# MobilityEliminationController.net
KiCad netlist of a schematic drawn in EAGLE
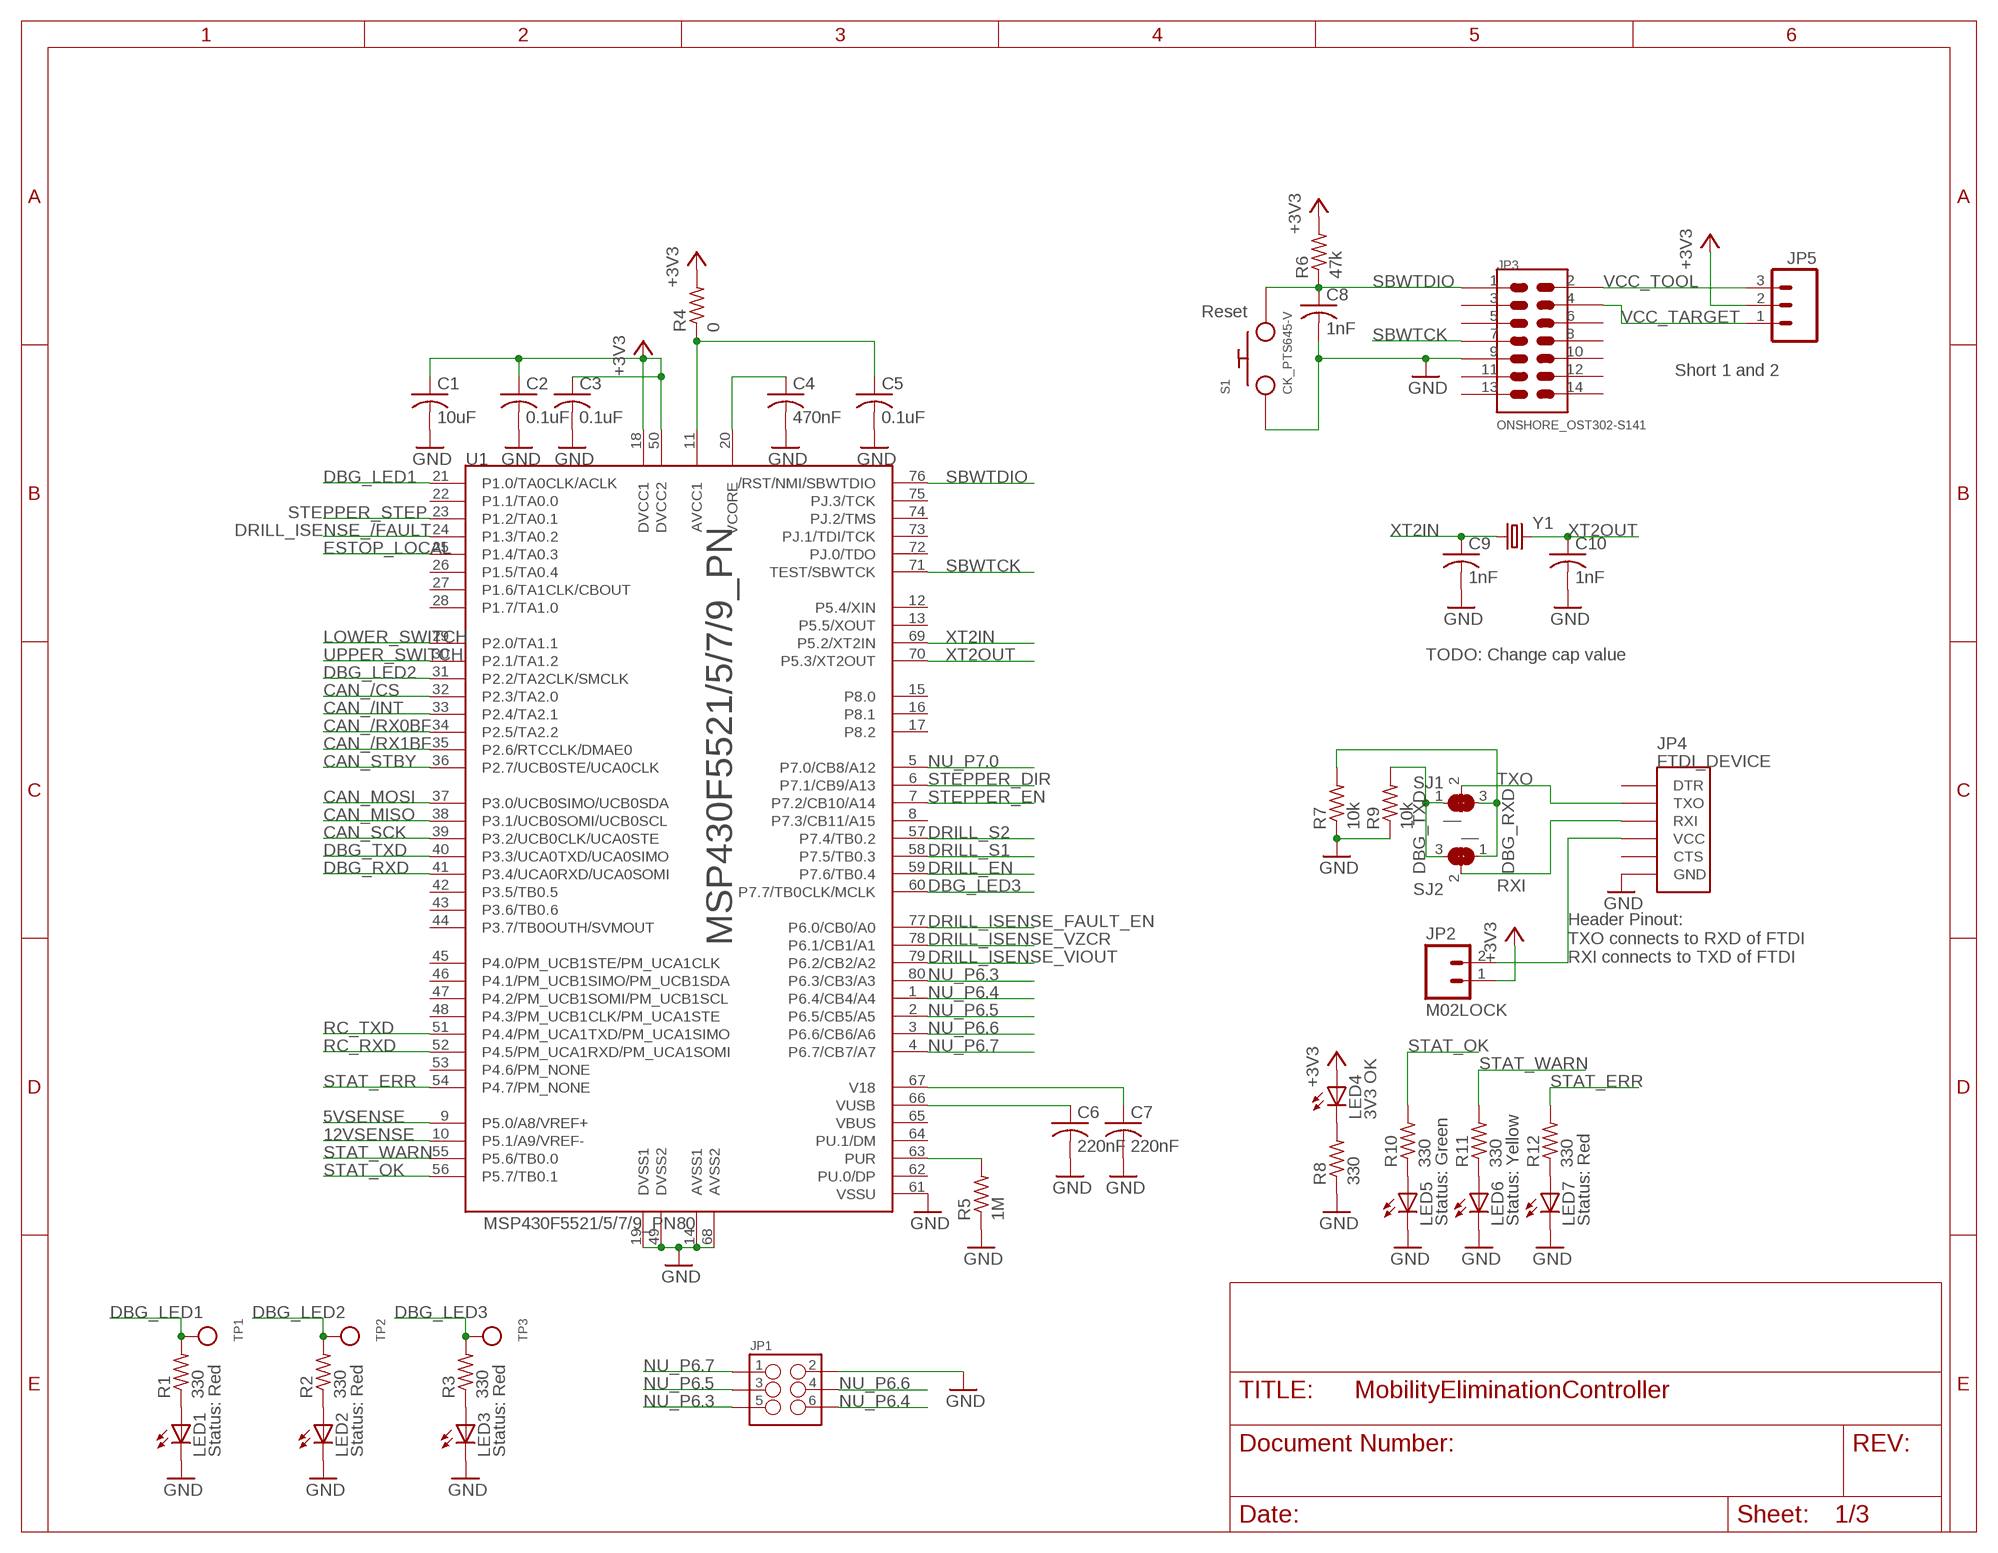
[diagram p0: schematic, sheet 1]
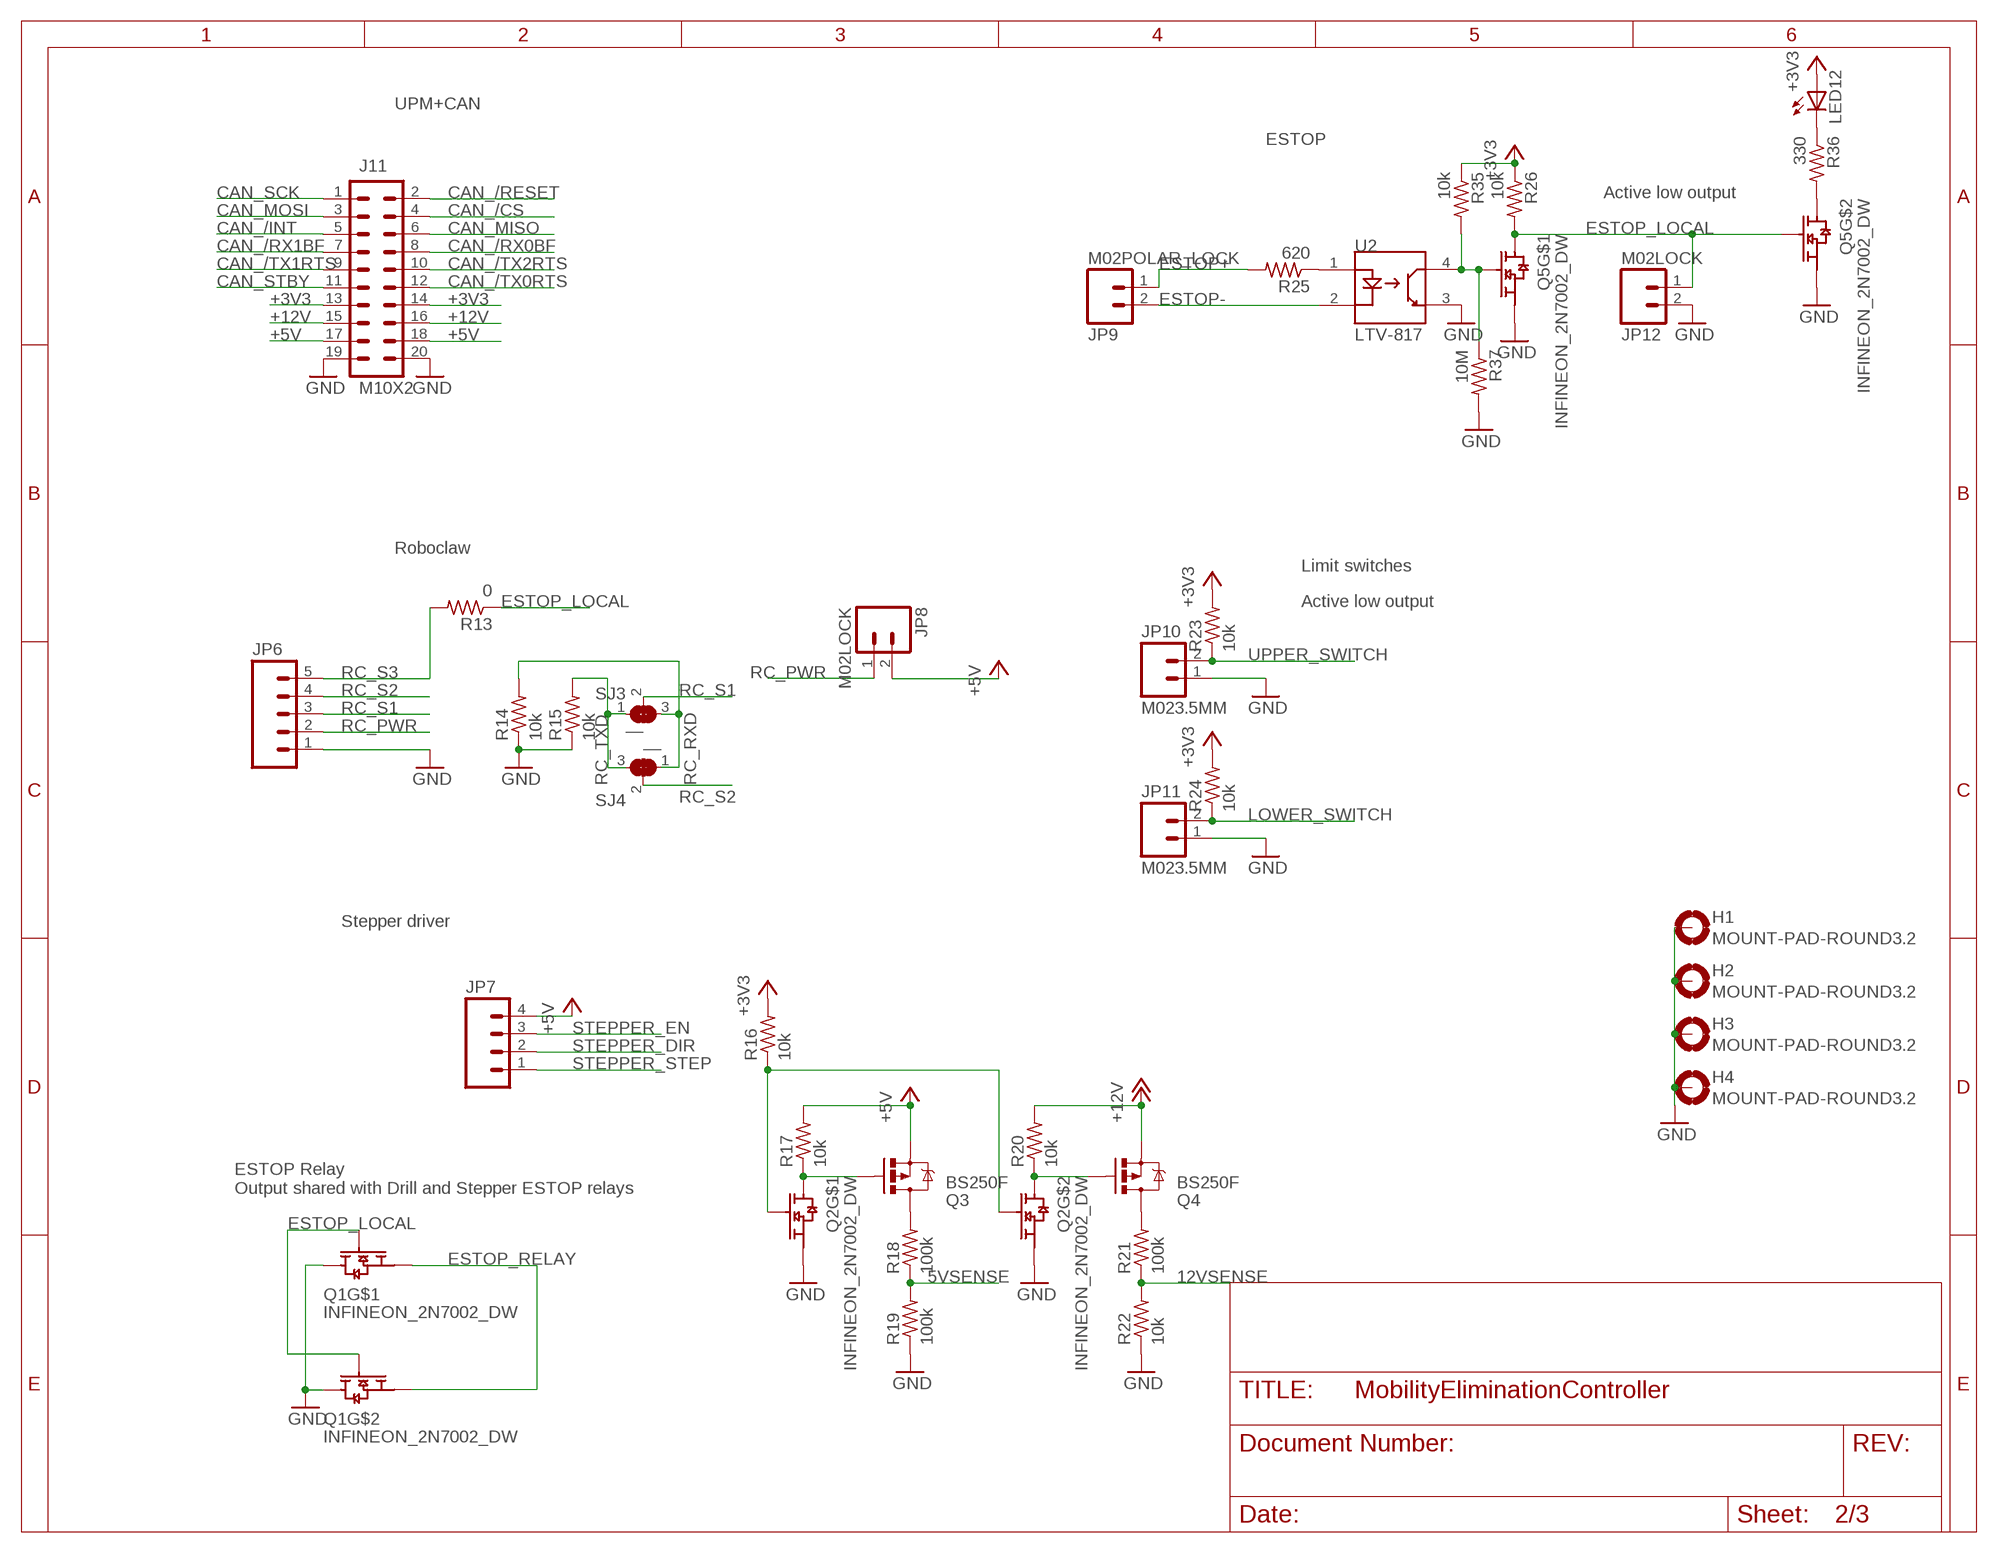
[diagram p1: schematic, sheet 2]
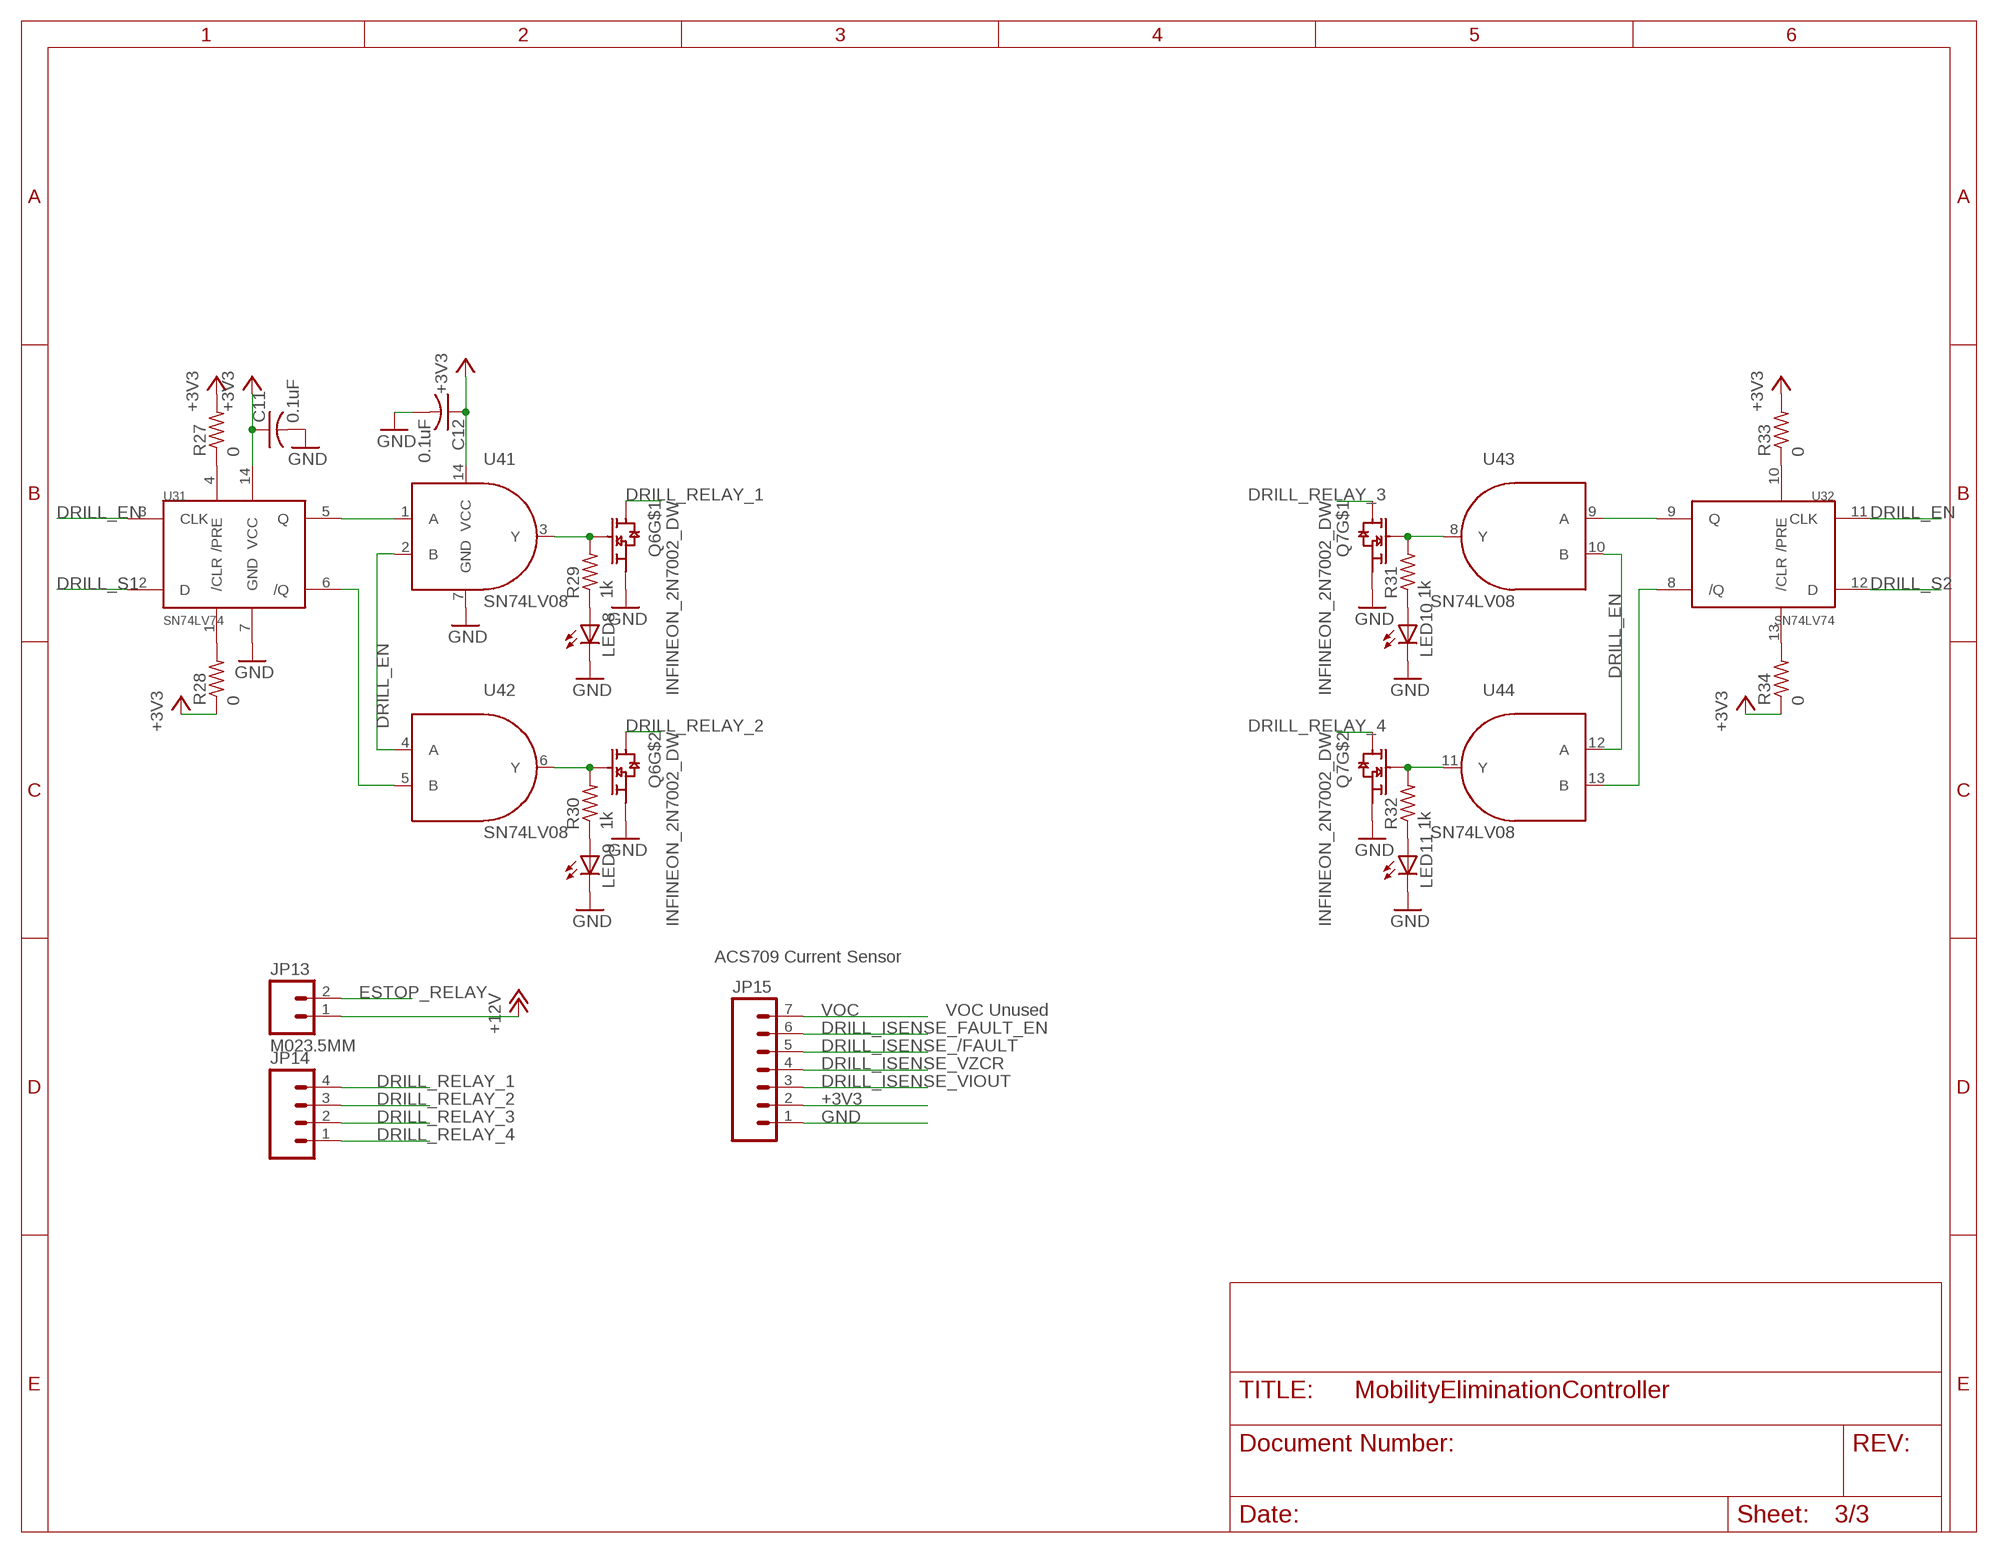
[diagram p2: schematic, sheet 3]

(export (version "E")
  (design (tool "Eeschema 10.0.6"))
  (components
    (comp (ref "C1")
      (value "10uF")
      (footprint "eagle-import:C0805")
      (libsource (lib "eagle-import") (part "C-USC0805"))
    )
    (comp (ref "C2")
      (value "0.1uF")
      (footprint "eagle-import:C0603")
      (libsource (lib "eagle-import") (part "C-USC0603"))
    )
    (comp (ref "C3")
      (value "0.1uF")
      (footprint "eagle-import:C0603")
      (libsource (lib "eagle-import") (part "C-USC0603"))
    )
    (comp (ref "C4")
      (value "470nF")
      (footprint "eagle-import:C0603")
      (libsource (lib "eagle-import") (part "C-USC0603"))
    )
    (comp (ref "C5")
      (value "0.1uF")
      (footprint "eagle-import:C0603")
      (libsource (lib "eagle-import") (part "C-USC0603"))
    )
    (comp (ref "C6")
      (value "220nF")
      (footprint "eagle-import:C0603")
      (libsource (lib "eagle-import") (part "C-USC0603"))
    )
    (comp (ref "C7")
      (value "220nF")
      (footprint "eagle-import:C0603")
      (libsource (lib "eagle-import") (part "C-USC0603"))
    )
    (comp (ref "C8")
      (value "1nF")
      (footprint "eagle-import:C0603")
      (libsource (lib "eagle-import") (part "C-USC0603"))
    )
    (comp (ref "C9")
      (value "1nF")
      (footprint "eagle-import:C0603")
      (libsource (lib "eagle-import") (part "C-USC0603"))
    )
    (comp (ref "C10")
      (value "1nF")
      (footprint "eagle-import:C0603")
      (libsource (lib "eagle-import") (part "C-USC0603"))
    )
    (comp (ref "JP1")
      (value "M03X22X3_SILK_SM")
      (footprint "eagle-import:2X3")
      (libsource (lib "eagle-import") (part "M03X22X3_SILK_SM"))
    )
    (comp (ref "JP2")
      (value "M02LOCK")
      (footprint "eagle-import:1X02_LOCK")
      (libsource (lib "eagle-import") (part "M02LOCK"))
    )
    (comp (ref "JP3")
      (value "ONSHORE_OST302-S141")
      (footprint "eagle-import:ONSHORE_OST302-S141")
      (libsource (lib "eagle-import") (part "ONSHORE_OST302-S141"))
    )
    (comp (ref "JP4")
      (value "FTDI_DEVICE")
      (footprint "eagle-import:FTDI_DEVICE_SIDE")
      (libsource (lib "eagle-import") (part "FTDI_DEVICE"))
    )
    (comp (ref "JP5")
      (value "M03LOCK")
      (footprint "eagle-import:1X03_LOCK")
      (libsource (lib "eagle-import") (part "M03LOCK"))
    )
    (comp (ref "LED1")
      (value "Status: Red")
      (footprint "eagle-import:LED-0603")
      (libsource (lib "eagle-import") (part "LED0603"))
    )
    (comp (ref "LED2")
      (value "Status: Red")
      (footprint "eagle-import:LED-0603")
      (libsource (lib "eagle-import") (part "LED0603"))
    )
    (comp (ref "LED3")
      (value "Status: Red")
      (footprint "eagle-import:LED-0603")
      (libsource (lib "eagle-import") (part "LED0603"))
    )
    (comp (ref "LED4")
      (value "3V3 OK")
      (footprint "eagle-import:LED-0603")
      (libsource (lib "eagle-import") (part "LED0603"))
    )
    (comp (ref "LED5")
      (value "Status: Green")
      (footprint "eagle-import:LED-0603")
      (libsource (lib "eagle-import") (part "LED0603"))
    )
    (comp (ref "LED6")
      (value "Status: Yellow")
      (footprint "eagle-import:LED-0603")
      (libsource (lib "eagle-import") (part "LED0603"))
    )
    (comp (ref "LED7")
      (value "Status: Red")
      (footprint "eagle-import:LED-0603")
      (libsource (lib "eagle-import") (part "LED0603"))
    )
    (comp (ref "R1")
      (value "330")
      (footprint "eagle-import:R0603")
      (libsource (lib "eagle-import") (part "R-US_R0603"))
    )
    (comp (ref "R2")
      (value "330")
      (footprint "eagle-import:R0603")
      (libsource (lib "eagle-import") (part "R-US_R0603"))
    )
    (comp (ref "R3")
      (value "330")
      (footprint "eagle-import:R0603")
      (libsource (lib "eagle-import") (part "R-US_R0603"))
    )
    (comp (ref "R4")
      (value "0")
      (footprint "eagle-import:R0603")
      (libsource (lib "eagle-import") (part "R-US_R0603"))
    )
    (comp (ref "R5")
      (value "1M")
      (footprint "eagle-import:R0603")
      (libsource (lib "eagle-import") (part "R-US_R0603"))
    )
    (comp (ref "R6")
      (value "47k")
      (footprint "eagle-import:R0603")
      (libsource (lib "eagle-import") (part "R-US_R0603"))
    )
    (comp (ref "R7")
      (value "10k")
      (footprint "eagle-import:R0603")
      (libsource (lib "eagle-import") (part "R-US_R0603"))
    )
    (comp (ref "R8")
      (value "330")
      (footprint "eagle-import:R0603")
      (libsource (lib "eagle-import") (part "R-US_R0603"))
    )
    (comp (ref "R9")
      (value "10k")
      (footprint "eagle-import:R0603")
      (libsource (lib "eagle-import") (part "R-US_R0603"))
    )
    (comp (ref "R10")
      (value "330")
      (footprint "eagle-import:R0603")
      (libsource (lib "eagle-import") (part "R-US_R0603"))
    )
    (comp (ref "R11")
      (value "330")
      (footprint "eagle-import:R0603")
      (libsource (lib "eagle-import") (part "R-US_R0603"))
    )
    (comp (ref "R12")
      (value "330")
      (footprint "eagle-import:R0603")
      (libsource (lib "eagle-import") (part "R-US_R0603"))
    )
    (comp (ref "S1")
      (value "CK_PTS645-V")
      (footprint "eagle-import:CK_PTS645-V")
      (libsource (lib "eagle-import") (part "CK_PTS645-V"))
    )
    (comp (ref "SJ1")
      (value "SOLDERJUMPER_2WAY0603")
      (footprint "eagle-import:SOLDERJUMPER_2WAY_OPEN_0603")
      (libsource (lib "eagle-import") (part "SOLDERJUMPER_2WAY0603"))
    )
    (comp (ref "SJ2")
      (value "SOLDERJUMPER_2WAY0603")
      (footprint "eagle-import:SOLDERJUMPER_2WAY_OPEN_0603")
      (libsource (lib "eagle-import") (part "SOLDERJUMPER_2WAY0603"))
    )
    (comp (ref "TP1")
      (value "TESTPOINT0.1\"")
      (footprint "eagle-import:1X01_ROUND")
      (libsource (lib "eagle-import") (part "TESTPOINT0.1{dblquote}"))
    )
    (comp (ref "TP2")
      (value "TESTPOINT0.1\"")
      (footprint "eagle-import:1X01_ROUND")
      (libsource (lib "eagle-import") (part "TESTPOINT0.1{dblquote}"))
    )
    (comp (ref "TP3")
      (value "TESTPOINT0.1\"")
      (footprint "eagle-import:1X01_ROUND")
      (libsource (lib "eagle-import") (part "TESTPOINT0.1{dblquote}"))
    )
    (comp (ref "U1")
      (value "MSP430F5521/5/7/9_PN80")
      (footprint "eagle-import:PN80")
      (libsource (lib "eagle-import") (part "MSP430F5521/5/7/9_PN80"))
    )
    (comp (ref "Y1")
      (value "CRYSTALHC49UV")
      (footprint "eagle-import:HC49U-V")
      (libsource (lib "eagle-import") (part "CRYSTALHC49UV"))
    )
    (comp (ref "C11")
      (value "0.1uF")
      (footprint "eagle-import:C0603")
      (libsource (lib "eagle-import") (part "C-USC0603"))
    )
    (comp (ref "C12")
      (value "0.1uF")
      (footprint "eagle-import:C0603")
      (libsource (lib "eagle-import") (part "C-USC0603"))
    )
    (comp (ref "JP13")
      (value "M023.5MM")
      (footprint "eagle-import:SCREWTERMINAL-3.5MM-2")
      (libsource (lib "eagle-import") (part "M023.5MM"))
    )
    (comp (ref "JP14")
      (value "M04SCREW")
      (footprint "eagle-import:SCREWTERMINAL-3.5MM-4")
      (libsource (lib "eagle-import") (part "M04SCREW"))
    )
    (comp (ref "JP15")
      (value "M07")
      (footprint "eagle-import:1X07")
      (libsource (lib "eagle-import") (part "M07"))
    )
    (comp (ref "LED8")
      (value "LED0603")
      (footprint "eagle-import:LED-0603")
      (libsource (lib "eagle-import") (part "LED0603"))
    )
    (comp (ref "LED9")
      (value "LED0603")
      (footprint "eagle-import:LED-0603")
      (libsource (lib "eagle-import") (part "LED0603"))
    )
    (comp (ref "LED10")
      (value "LED0603")
      (footprint "eagle-import:LED-0603")
      (libsource (lib "eagle-import") (part "LED0603"))
    )
    (comp (ref "LED11")
      (value "LED0603")
      (footprint "eagle-import:LED-0603")
      (libsource (lib "eagle-import") (part "LED0603"))
    )
    (comp (ref "Q6")
      (value "INFINEON_2N7002_DW")
      (footprint "eagle-import:INFINEON_SOT363")
      (libsource (lib "eagle-import") (part "INFINEON_2N7002_DW"))
    )
    (comp (ref "Q7")
      (value "INFINEON_2N7002_DW")
      (footprint "eagle-import:INFINEON_SOT363")
      (libsource (lib "eagle-import") (part "INFINEON_2N7002_DW"))
    )
    (comp (ref "R27")
      (value "0")
      (footprint "eagle-import:R0603")
      (libsource (lib "eagle-import") (part "R-US_R0603"))
    )
    (comp (ref "R28")
      (value "0")
      (footprint "eagle-import:R0603")
      (libsource (lib "eagle-import") (part "R-US_R0603"))
    )
    (comp (ref "R29")
      (value "1k")
      (footprint "eagle-import:R0603")
      (libsource (lib "eagle-import") (part "R-US_R0603"))
    )
    (comp (ref "R30")
      (value "1k")
      (footprint "eagle-import:R0603")
      (libsource (lib "eagle-import") (part "R-US_R0603"))
    )
    (comp (ref "R31")
      (value "1k")
      (footprint "eagle-import:R0603")
      (libsource (lib "eagle-import") (part "R-US_R0603"))
    )
    (comp (ref "R32")
      (value "1k")
      (footprint "eagle-import:R0603")
      (libsource (lib "eagle-import") (part "R-US_R0603"))
    )
    (comp (ref "R33")
      (value "0")
      (footprint "eagle-import:R0603")
      (libsource (lib "eagle-import") (part "R-US_R0603"))
    )
    (comp (ref "R34")
      (value "0")
      (footprint "eagle-import:R0603")
      (libsource (lib "eagle-import") (part "R-US_R0603"))
    )
    (comp (ref "U3")
      (value "SN74LV74")
      (footprint "eagle-import:TI_D_R-PDSO-G14_SOIC14")
      (libsource (lib "eagle-import") (part "SN74LV74"))
    )
    (comp (ref "U4")
      (value "SN74LV08")
      (footprint "eagle-import:TI_D_R-PDSO-G14_SOIC14")
      (libsource (lib "eagle-import") (part "SN74LV08"))
    )
    (comp (ref "H1")
      (value "MOUNT-PAD-ROUND3.2")
      (footprint "eagle-import:3,2-PAD")
      (libsource (lib "eagle-import") (part "MOUNT-PAD-ROUND3.2"))
    )
    (comp (ref "H2")
      (value "MOUNT-PAD-ROUND3.2")
      (footprint "eagle-import:3,2-PAD")
      (libsource (lib "eagle-import") (part "MOUNT-PAD-ROUND3.2"))
    )
    (comp (ref "H3")
      (value "MOUNT-PAD-ROUND3.2")
      (footprint "eagle-import:3,2-PAD")
      (libsource (lib "eagle-import") (part "MOUNT-PAD-ROUND3.2"))
    )
    (comp (ref "H4")
      (value "MOUNT-PAD-ROUND3.2")
      (footprint "eagle-import:3,2-PAD")
      (libsource (lib "eagle-import") (part "MOUNT-PAD-ROUND3.2"))
    )
    (comp (ref "J11")
      (value "M10X2")
      (footprint "eagle-import:2X10")
      (libsource (lib "eagle-import") (part "M10X2"))
    )
    (comp (ref "JP6")
      (value "M05LOCK")
      (footprint "eagle-import:1X05_LOCK")
      (libsource (lib "eagle-import") (part "M05LOCK"))
    )
    (comp (ref "JP7")
      (value "M04SCREW")
      (footprint "eagle-import:SCREWTERMINAL-3.5MM-4")
      (libsource (lib "eagle-import") (part "M04SCREW"))
    )
    (comp (ref "JP8")
      (value "M02LOCK")
      (footprint "eagle-import:1X02_LOCK")
      (libsource (lib "eagle-import") (part "M02LOCK"))
    )
    (comp (ref "JP9")
      (value "M02POLAR_LOCK")
      (footprint "eagle-import:MOLEX-1X2_LOCK")
      (libsource (lib "eagle-import") (part "M02POLAR_LOCK"))
    )
    (comp (ref "JP10")
      (value "M023.5MM")
      (footprint "eagle-import:SCREWTERMINAL-3.5MM-2")
      (libsource (lib "eagle-import") (part "M023.5MM"))
    )
    (comp (ref "JP11")
      (value "M023.5MM")
      (footprint "eagle-import:SCREWTERMINAL-3.5MM-2")
      (libsource (lib "eagle-import") (part "M023.5MM"))
    )
    (comp (ref "JP12")
      (value "M02LOCK")
      (footprint "eagle-import:1X02_LOCK")
      (libsource (lib "eagle-import") (part "M02LOCK"))
    )
    (comp (ref "LED12")
      (value "LED0603")
      (footprint "eagle-import:LED-0603")
      (libsource (lib "eagle-import") (part "LED0603"))
    )
    (comp (ref "Q1")
      (value "INFINEON_2N7002_DW")
      (footprint "eagle-import:INFINEON_SOT363")
      (libsource (lib "eagle-import") (part "INFINEON_2N7002_DW"))
    )
    (comp (ref "Q2")
      (value "INFINEON_2N7002_DW")
      (footprint "eagle-import:INFINEON_SOT363")
      (libsource (lib "eagle-import") (part "INFINEON_2N7002_DW"))
    )
    (comp (ref "Q3")
      (value "BS250F")
      (footprint "eagle-import:SOT23-3")
      (libsource (lib "eagle-import") (part "MOSFET-PCHANNELSMD"))
    )
    (comp (ref "Q4")
      (value "BS250F")
      (footprint "eagle-import:SOT23-3")
      (libsource (lib "eagle-import") (part "MOSFET-PCHANNELSMD"))
    )
    (comp (ref "Q5")
      (value "INFINEON_2N7002_DW")
      (footprint "eagle-import:INFINEON_SOT363")
      (libsource (lib "eagle-import") (part "INFINEON_2N7002_DW"))
    )
    (comp (ref "R13")
      (value "0")
      (footprint "eagle-import:R0603")
      (libsource (lib "eagle-import") (part "R-US_R0603"))
    )
    (comp (ref "R14")
      (value "10k")
      (footprint "eagle-import:R0603")
      (libsource (lib "eagle-import") (part "R-US_R0603"))
    )
    (comp (ref "R15")
      (value "10k")
      (footprint "eagle-import:R0603")
      (libsource (lib "eagle-import") (part "R-US_R0603"))
    )
    (comp (ref "R16")
      (value "10k")
      (footprint "eagle-import:R0603")
      (libsource (lib "eagle-import") (part "R-US_R0603"))
    )
    (comp (ref "R17")
      (value "10k")
      (footprint "eagle-import:R0603")
      (libsource (lib "eagle-import") (part "R-US_R0603"))
    )
    (comp (ref "R18")
      (value "100k")
      (footprint "eagle-import:R0603")
      (libsource (lib "eagle-import") (part "R-US_R0603"))
    )
    (comp (ref "R19")
      (value "100k")
      (footprint "eagle-import:R0603")
      (libsource (lib "eagle-import") (part "R-US_R0603"))
    )
    (comp (ref "R20")
      (value "10k")
      (footprint "eagle-import:R0603")
      (libsource (lib "eagle-import") (part "R-US_R0603"))
    )
    (comp (ref "R21")
      (value "100k")
      (footprint "eagle-import:R0603")
      (libsource (lib "eagle-import") (part "R-US_R0603"))
    )
    (comp (ref "R22")
      (value "10k")
      (footprint "eagle-import:R0603")
      (libsource (lib "eagle-import") (part "R-US_R0603"))
    )
    (comp (ref "R23")
      (value "10k")
      (footprint "eagle-import:R0603")
      (libsource (lib "eagle-import") (part "R-US_R0603"))
    )
    (comp (ref "R24")
      (value "10k")
      (footprint "eagle-import:R0603")
      (libsource (lib "eagle-import") (part "R-US_R0603"))
    )
    (comp (ref "R25")
      (value "620")
      (footprint "eagle-import:R0603")
      (libsource (lib "eagle-import") (part "R-US_R0603"))
    )
    (comp (ref "R26")
      (value "10k")
      (footprint "eagle-import:R0603")
      (libsource (lib "eagle-import") (part "R-US_R0603"))
    )
    (comp (ref "R35")
      (value "10k")
      (footprint "eagle-import:R0603")
      (libsource (lib "eagle-import") (part "R-US_R0603"))
    )
    (comp (ref "R36")
      (value "330")
      (footprint "eagle-import:R0603")
      (libsource (lib "eagle-import") (part "R-US_R0603"))
    )
    (comp (ref "R37")
      (value "10M")
      (footprint "eagle-import:R0603")
      (libsource (lib "eagle-import") (part "R-US_R0603"))
    )
    (comp (ref "SJ3")
      (value "SOLDERJUMPER_2WAY0603")
      (footprint "eagle-import:SOLDERJUMPER_2WAY_OPEN_0603")
      (libsource (lib "eagle-import") (part "SOLDERJUMPER_2WAY0603"))
    )
    (comp (ref "SJ4")
      (value "SOLDERJUMPER_2WAY0603")
      (footprint "eagle-import:SOLDERJUMPER_2WAY_OPEN_0603")
      (libsource (lib "eagle-import") (part "SOLDERJUMPER_2WAY0603"))
    )
    (comp (ref "U2")
      (value "LTV-817")
      (footprint "eagle-import:LITEON_DIL04_.3")
      (libsource (lib "eagle-import") (part "LTV-817"))
    )
  )
  (nets
    (net (code "1") (name "+3V3") (class "Default")
      (node (ref "C1") (pin "1") (pinfunction "1_1") (pintype "passive"))
      (node (ref "C11") (pin "1") (pinfunction "1_1") (pintype "passive"))
      (node (ref "C12") (pin "1") (pinfunction "1_1") (pintype "passive"))
      (node (ref "C2") (pin "1") (pinfunction "1_1") (pintype "passive"))
      (node (ref "C3") (pin "1") (pinfunction "1_1") (pintype "passive"))
      (node (ref "J11") (pin "13") (pinfunction "13_13") (pintype "passive"))
      (node (ref "J11") (pin "14") (pinfunction "14_14") (pintype "passive"))
      (node (ref "JP15") (pin "2") (pinfunction "2_2") (pintype "passive"))
      (node (ref "JP2") (pin "1") (pinfunction "1_1") (pintype "passive"))
      (node (ref "JP5") (pin "2") (pinfunction "2_2") (pintype "passive"))
      (node (ref "LED12") (pin "A") (pinfunction "A_A") (pintype "passive"))
      (node (ref "LED4") (pin "A") (pinfunction "A_A") (pintype "passive"))
      (node (ref "R16") (pin "2") (pinfunction "2_2") (pintype "passive"))
      (node (ref "R23") (pin "2") (pinfunction "2_2") (pintype "passive"))
      (node (ref "R24") (pin "2") (pinfunction "2_2") (pintype "passive"))
      (node (ref "R26") (pin "1") (pinfunction "1_1") (pintype "passive"))
      (node (ref "R27") (pin "2") (pinfunction "2_2") (pintype "passive"))
      (node (ref "R28") (pin "1") (pinfunction "1_1") (pintype "passive"))
      (node (ref "R33") (pin "2") (pinfunction "2_2") (pintype "passive"))
      (node (ref "R34") (pin "1") (pinfunction "1_1") (pintype "passive"))
      (node (ref "R35") (pin "1") (pinfunction "1_1") (pintype "passive"))
      (node (ref "R4") (pin "2") (pinfunction "2_2") (pintype "passive"))
      (node (ref "R6") (pin "2") (pinfunction "2_2") (pintype "passive"))
      (node (ref "U1") (pin "18") (pinfunction "DVCC1_18") (pintype "bidirectional"))
      (node (ref "U1") (pin "50") (pinfunction "DVCC2_50") (pintype "bidirectional"))
      (node (ref "U3") (pin "14") (pinfunction "VCC_14") (pintype "bidirectional"))
      (node (ref "U4") (pin "14") (pinfunction "VCC_14") (pintype "bidirectional"))
    )
    (net (code "2") (name "+5V") (class "Default")
      (node (ref "J11") (pin "17") (pinfunction "17_17") (pintype "passive"))
      (node (ref "J11") (pin "18") (pinfunction "18_18") (pintype "passive"))
      (node (ref "JP7") (pin "4") (pinfunction "4_4") (pintype "passive"))
      (node (ref "JP8") (pin "2") (pinfunction "2_2") (pintype "passive"))
      (node (ref "Q3") (pin "2") (pinfunction "S_2") (pintype "passive"))
      (node (ref "R17") (pin "2") (pinfunction "2_2") (pintype "passive"))
    )
    (net (code "3") (name "+12V") (class "Default")
      (node (ref "J11") (pin "15") (pinfunction "15_15") (pintype "passive"))
      (node (ref "J11") (pin "16") (pinfunction "16_16") (pintype "passive"))
      (node (ref "JP13") (pin "1") (pinfunction "1_1") (pintype "passive"))
      (node (ref "Q4") (pin "2") (pinfunction "S_2") (pintype "passive"))
      (node (ref "R20") (pin "2") (pinfunction "2_2") (pintype "passive"))
    )
    (net (code "4") (name "5VSENSE") (class "Default")
      (node (ref "R18") (pin "1") (pinfunction "1_1") (pintype "passive"))
      (node (ref "R19") (pin "2") (pinfunction "2_2") (pintype "passive"))
      (node (ref "U1") (pin "9") (pinfunction "P5.0/A8/VREF+_9") (pintype "bidirectional"))
    )
    (net (code "5") (name "12VSENSE") (class "Default")
      (node (ref "R21") (pin "1") (pinfunction "1_1") (pintype "passive"))
      (node (ref "R22") (pin "2") (pinfunction "2_2") (pintype "passive"))
      (node (ref "U1") (pin "10") (pinfunction "P5.1/A9/VREF-_10") (pintype "bidirectional"))
    )
    (net (code "6") (name "CAN_MISO") (class "Default")
      (node (ref "J11") (pin "6") (pinfunction "6_6") (pintype "passive"))
      (node (ref "U1") (pin "38") (pinfunction "P3.1/UCB0SOMI/UCB0SCL_38") (pintype "bidirectional"))
    )
    (net (code "7") (name "CAN_MOSI") (class "Default")
      (node (ref "J11") (pin "3") (pinfunction "3_3") (pintype "passive"))
      (node (ref "U1") (pin "37") (pinfunction "P3.0/UCB0SIMO/UCB0SDA_37") (pintype "bidirectional"))
    )
    (net (code "8") (name "CAN_SCK") (class "Default")
      (node (ref "J11") (pin "1") (pinfunction "1_1") (pintype "passive"))
      (node (ref "U1") (pin "39") (pinfunction "P3.2/UCB0CLK/UCA0STE_39") (pintype "bidirectional"))
    )
    (net (code "9") (name "CAN_STBY") (class "Default")
      (node (ref "J11") (pin "11") (pinfunction "11_11") (pintype "passive"))
      (node (ref "U1") (pin "36") (pinfunction "P2.7/UCB0STE/UCA0CLK_36") (pintype "bidirectional"))
    )
    (net (code "10") (name "CAN_{slash}CS") (class "Default")
      (node (ref "J11") (pin "4") (pinfunction "4_4") (pintype "passive"))
      (node (ref "U1") (pin "32") (pinfunction "P2.3/TA2.0_32") (pintype "bidirectional"))
    )
    (net (code "11") (name "CAN_{slash}INT") (class "Default")
      (node (ref "J11") (pin "5") (pinfunction "5_5") (pintype "passive"))
      (node (ref "U1") (pin "33") (pinfunction "P2.4/TA2.1_33") (pintype "bidirectional"))
    )
    (net (code "12") (name "CAN_{slash}RESET") (class "Default")
      (node (ref "J11") (pin "2") (pinfunction "2_2") (pintype "passive"))
    )
    (net (code "13") (name "CAN_{slash}RX0BF") (class "Default")
      (node (ref "J11") (pin "8") (pinfunction "8_8") (pintype "passive"))
      (node (ref "U1") (pin "34") (pinfunction "P2.5/TA2.2_34") (pintype "bidirectional"))
    )
    (net (code "14") (name "CAN_{slash}RX1BF") (class "Default")
      (node (ref "J11") (pin "7") (pinfunction "7_7") (pintype "passive"))
      (node (ref "U1") (pin "35") (pinfunction "P2.6/RTCCLK/DMAE0_35") (pintype "bidirectional"))
    )
    (net (code "15") (name "CAN_{slash}TX0RTS") (class "Default")
      (node (ref "J11") (pin "12") (pinfunction "12_12") (pintype "passive"))
    )
    (net (code "16") (name "CAN_{slash}TX1RTS") (class "Default")
      (node (ref "J11") (pin "9") (pinfunction "9_9") (pintype "passive"))
    )
    (net (code "17") (name "CAN_{slash}TX2RTS") (class "Default")
      (node (ref "J11") (pin "10") (pinfunction "10_10") (pintype "passive"))
    )
    (net (code "18") (name "DBG_LED1") (class "Default")
      (node (ref "R1") (pin "2") (pinfunction "2_2") (pintype "passive"))
      (node (ref "TP1") (pin "1") (pinfunction "P$1_1") (pintype "bidirectional"))
      (node (ref "U1") (pin "21") (pinfunction "P1.0/TA0CLK/ACLK_21") (pintype "bidirectional"))
    )
    (net (code "19") (name "DBG_LED2") (class "Default")
      (node (ref "R2") (pin "2") (pinfunction "2_2") (pintype "passive"))
      (node (ref "TP2") (pin "1") (pinfunction "P$1_1") (pintype "bidirectional"))
      (node (ref "U1") (pin "31") (pinfunction "P2.2/TA2CLK/SMCLK_31") (pintype "bidirectional"))
    )
    (net (code "20") (name "DBG_LED3") (class "Default")
      (node (ref "R3") (pin "2") (pinfunction "2_2") (pintype "passive"))
      (node (ref "TP3") (pin "1") (pinfunction "P$1_1") (pintype "bidirectional"))
      (node (ref "U1") (pin "60") (pinfunction "P7.7/TB0CLK/MCLK_60") (pintype "bidirectional"))
    )
    (net (code "21") (name "DBG_RXD") (class "Default")
      (node (ref "R7") (pin "2") (pinfunction "2_2") (pintype "passive"))
      (node (ref "SJ1") (pin "3") (pinfunction "3_3") (pintype "passive"))
      (node (ref "SJ2") (pin "1") (pinfunction "1_1") (pintype "passive"))
      (node (ref "U1") (pin "41") (pinfunction "P3.4/UCA0RXD/UCA0SOMI_41") (pintype "bidirectional"))
    )
    (net (code "22") (name "DBG_TXD") (class "Default")
      (node (ref "R9") (pin "2") (pinfunction "2_2") (pintype "passive"))
      (node (ref "SJ1") (pin "1") (pinfunction "1_1") (pintype "passive"))
      (node (ref "SJ2") (pin "3") (pinfunction "3_3") (pintype "passive"))
      (node (ref "U1") (pin "40") (pinfunction "P3.3/UCA0TXD/UCA0SIMO_40") (pintype "bidirectional"))
    )
    (net (code "23") (name "DRILL_EN") (class "Default")
      (node (ref "U1") (pin "59") (pinfunction "P7.6/TB0.4_59") (pintype "bidirectional"))
      (node (ref "U3") (pin "11") (pinfunction "CLK_11") (pintype "bidirectional"))
      (node (ref "U3") (pin "3") (pinfunction "CLK_3") (pintype "bidirectional"))
      (node (ref "U4") (pin "10") (pinfunction "B_10") (pintype "bidirectional"))
      (node (ref "U4") (pin "12") (pinfunction "A_12") (pintype "bidirectional"))
      (node (ref "U4") (pin "2") (pinfunction "B_2") (pintype "bidirectional"))
      (node (ref "U4") (pin "4") (pinfunction "A_4") (pintype "bidirectional"))
    )
    (net (code "24") (name "DRILL_ISENSE_FAULT_EN") (class "Default")
      (node (ref "JP15") (pin "6") (pinfunction "6_6") (pintype "passive"))
      (node (ref "U1") (pin "77") (pinfunction "P6.0/CB0/A0_77") (pintype "bidirectional"))
    )
    (net (code "25") (name "DRILL_ISENSE_VIOUT") (class "Default")
      (node (ref "JP15") (pin "3") (pinfunction "3_3") (pintype "passive"))
      (node (ref "U1") (pin "79") (pinfunction "P6.2/CB2/A2_79") (pintype "bidirectional"))
    )
    (net (code "26") (name "DRILL_ISENSE_VZCR") (class "Default")
      (node (ref "JP15") (pin "4") (pinfunction "4_4") (pintype "passive"))
      (node (ref "U1") (pin "78") (pinfunction "P6.1/CB1/A1_78") (pintype "bidirectional"))
    )
    (net (code "27") (name "DRILL_ISENSE_{slash}FAULT") (class "Default")
      (node (ref "JP15") (pin "5") (pinfunction "5_5") (pintype "passive"))
      (node (ref "U1") (pin "24") (pinfunction "P1.3/TA0.2_24") (pintype "bidirectional"))
    )
    (net (code "28") (name "DRILL_RELAY_1") (class "Default")
      (node (ref "JP14") (pin "4") (pinfunction "4_4") (pintype "passive"))
      (node (ref "Q6") (pin "6") (pinfunction "DRAIN_6") (pintype "bidirectional"))
    )
    (net (code "29") (name "DRILL_RELAY_2") (class "Default")
      (node (ref "JP14") (pin "3") (pinfunction "3_3") (pintype "passive"))
      (node (ref "Q6") (pin "3") (pinfunction "DRAIN_3") (pintype "bidirectional"))
    )
    (net (code "30") (name "DRILL_RELAY_3") (class "Default")
      (node (ref "JP14") (pin "2") (pinfunction "2_2") (pintype "passive"))
      (node (ref "Q7") (pin "6") (pinfunction "DRAIN_6") (pintype "bidirectional"))
    )
    (net (code "31") (name "DRILL_RELAY_4") (class "Default")
      (node (ref "JP14") (pin "1") (pinfunction "1_1") (pintype "passive"))
      (node (ref "Q7") (pin "3") (pinfunction "DRAIN_3") (pintype "bidirectional"))
    )
    (net (code "32") (name "DRILL_S1") (class "Default")
      (node (ref "U1") (pin "58") (pinfunction "P7.5/TB0.3_58") (pintype "bidirectional"))
      (node (ref "U3") (pin "2") (pinfunction "D_2") (pintype "bidirectional"))
    )
    (net (code "33") (name "DRILL_S2") (class "Default")
      (node (ref "U1") (pin "57") (pinfunction "P7.4/TB0.2_57") (pintype "bidirectional"))
      (node (ref "U3") (pin "12") (pinfunction "D_12") (pintype "bidirectional"))
    )
    (net (code "34") (name "ESTOP+") (class "Default")
      (node (ref "JP9") (pin "1") (pinfunction "1_1") (pintype "passive"))
      (node (ref "R25") (pin "2") (pinfunction "2_2") (pintype "passive"))
    )
    (net (code "35") (name "ESTOP-") (class "Default")
      (node (ref "JP9") (pin "2") (pinfunction "2_2") (pintype "passive"))
      (node (ref "U2") (pin "2") (pinfunction "2_2") (pintype "bidirectional"))
    )
    (net (code "36") (name "ESTOP_LOCAL") (class "Default")
      (node (ref "JP12") (pin "1") (pinfunction "1_1") (pintype "passive"))
      (node (ref "Q1") (pin "2") (pinfunction "GATE_2") (pintype "bidirectional"))
      (node (ref "Q1") (pin "5") (pinfunction "GATE_5") (pintype "bidirectional"))
      (node (ref "Q5") (pin "5") (pinfunction "GATE_5") (pintype "bidirectional"))
      (node (ref "Q5") (pin "6") (pinfunction "DRAIN_6") (pintype "bidirectional"))
      (node (ref "R13") (pin "1") (pinfunction "1_1") (pintype "passive"))
      (node (ref "R26") (pin "2") (pinfunction "2_2") (pintype "passive"))
      (node (ref "U1") (pin "25") (pinfunction "P1.4/TA0.3_25") (pintype "bidirectional"))
    )
    (net (code "37") (name "ESTOP_RELAY") (class "Default")
      (node (ref "JP13") (pin "2") (pinfunction "2_2") (pintype "passive"))
      (node (ref "Q1") (pin "1") (pinfunction "SOURCE_1") (pintype "bidirectional"))
      (node (ref "Q1") (pin "4") (pinfunction "SOURCE_4") (pintype "bidirectional"))
    )
    (net (code "38") (name "GND") (class "Default")
      (node (ref "C1") (pin "2") (pinfunction "2_2") (pintype "passive"))
      (node (ref "C10") (pin "2") (pinfunction "2_2") (pintype "passive"))
      (node (ref "C11") (pin "2") (pinfunction "2_2") (pintype "passive"))
      (node (ref "C12") (pin "2") (pinfunction "2_2") (pintype "passive"))
      (node (ref "C2") (pin "2") (pinfunction "2_2") (pintype "passive"))
      (node (ref "C3") (pin "2") (pinfunction "2_2") (pintype "passive"))
      (node (ref "C4") (pin "2") (pinfunction "2_2") (pintype "passive"))
      (node (ref "C5") (pin "2") (pinfunction "2_2") (pintype "passive"))
      (node (ref "C6") (pin "2") (pinfunction "2_2") (pintype "passive"))
      (node (ref "C7") (pin "2") (pinfunction "2_2") (pintype "passive"))
      (node (ref "C8") (pin "2") (pinfunction "2_2") (pintype "passive"))
      (node (ref "C9") (pin "2") (pinfunction "2_2") (pintype "passive"))
      (node (ref "H1") (pin "B3,2") (pinfunction "MOUNT_B3,2") (pintype "passive"))
      (node (ref "H2") (pin "B3,2") (pinfunction "MOUNT_B3,2") (pintype "passive"))
      (node (ref "H3") (pin "B3,2") (pinfunction "MOUNT_B3,2") (pintype "passive"))
      (node (ref "H4") (pin "B3,2") (pinfunction "MOUNT_B3,2") (pintype "passive"))
      (node (ref "J11") (pin "19") (pinfunction "19_19") (pintype "passive"))
      (node (ref "J11") (pin "20") (pinfunction "20_20") (pintype "passive"))
      (node (ref "JP1") (pin "2") (pinfunction "2_2") (pintype "bidirectional"))
      (node (ref "JP10") (pin "1") (pinfunction "1_1") (pintype "passive"))
      (node (ref "JP11") (pin "1") (pinfunction "1_1") (pintype "passive"))
      (node (ref "JP12") (pin "2") (pinfunction "2_2") (pintype "passive"))
      (node (ref "JP15") (pin "1") (pinfunction "1_1") (pintype "passive"))
      (node (ref "JP3") (pin "9") (pinfunction "9_9") (pintype "bidirectional"))
      (node (ref "JP4") (pin "P$6") (pinfunction "GND_P$6") (pintype "bidirectional"))
      (node (ref "JP6") (pin "1") (pinfunction "1_1") (pintype "passive"))
      (node (ref "LED1") (pin "C") (pinfunction "C_C") (pintype "passive"))
      (node (ref "LED10") (pin "C") (pinfunction "C_C") (pintype "passive"))
      (node (ref "LED11") (pin "C") (pinfunction "C_C") (pintype "passive"))
      (node (ref "LED2") (pin "C") (pinfunction "C_C") (pintype "passive"))
      (node (ref "LED3") (pin "C") (pinfunction "C_C") (pintype "passive"))
      (node (ref "LED5") (pin "C") (pinfunction "C_C") (pintype "passive"))
      (node (ref "LED6") (pin "C") (pinfunction "C_C") (pintype "passive"))
      (node (ref "LED7") (pin "C") (pinfunction "C_C") (pintype "passive"))
      (node (ref "LED8") (pin "C") (pinfunction "C_C") (pintype "passive"))
      (node (ref "LED9") (pin "C") (pinfunction "C_C") (pintype "passive"))
      (node (ref "Q1") (pin "3") (pinfunction "DRAIN_3") (pintype "bidirectional"))
      (node (ref "Q1") (pin "6") (pinfunction "DRAIN_6") (pintype "bidirectional"))
      (node (ref "Q2") (pin "1") (pinfunction "SOURCE_1") (pintype "bidirectional"))
      (node (ref "Q2") (pin "4") (pinfunction "SOURCE_4") (pintype "bidirectional"))
      (node (ref "Q5") (pin "1") (pinfunction "SOURCE_1") (pintype "bidirectional"))
      (node (ref "Q5") (pin "4") (pinfunction "SOURCE_4") (pintype "bidirectional"))
      (node (ref "Q6") (pin "1") (pinfunction "SOURCE_1") (pintype "bidirectional"))
      (node (ref "Q6") (pin "4") (pinfunction "SOURCE_4") (pintype "bidirectional"))
      (node (ref "Q7") (pin "1") (pinfunction "SOURCE_1") (pintype "bidirectional"))
      (node (ref "Q7") (pin "4") (pinfunction "SOURCE_4") (pintype "bidirectional"))
      (node (ref "R14") (pin "1") (pinfunction "1_1") (pintype "passive"))
      (node (ref "R15") (pin "1") (pinfunction "1_1") (pintype "passive"))
      (node (ref "R19") (pin "1") (pinfunction "1_1") (pintype "passive"))
      (node (ref "R22") (pin "1") (pinfunction "1_1") (pintype "passive"))
      (node (ref "R37") (pin "2") (pinfunction "2_2") (pintype "passive"))
      (node (ref "R5") (pin "1") (pinfunction "1_1") (pintype "passive"))
      (node (ref "R7") (pin "1") (pinfunction "1_1") (pintype "passive"))
      (node (ref "R8") (pin "1") (pinfunction "1_1") (pintype "passive"))
      (node (ref "R9") (pin "1") (pinfunction "1_1") (pintype "passive"))
      (node (ref "S1") (pin "1") (pinfunction "1_1") (pintype "bidirectional"))
      (node (ref "U1") (pin "14") (pinfunction "AVSS1_14") (pintype "bidirectional"))
      (node (ref "U1") (pin "19") (pinfunction "DVSS1_19") (pintype "bidirectional"))
      (node (ref "U1") (pin "49") (pinfunction "DVSS2_49") (pintype "bidirectional"))
      (node (ref "U1") (pin "61") (pinfunction "VSSU_61") (pintype "bidirectional"))
      (node (ref "U1") (pin "68") (pinfunction "AVSS2_68") (pintype "bidirectional"))
      (node (ref "U2") (pin "3") (pinfunction "3_3") (pintype "bidirectional"))
      (node (ref "U3") (pin "7") (pinfunction "GND_7") (pintype "bidirectional"))
      (node (ref "U4") (pin "7") (pinfunction "GND_7") (pintype "bidirectional"))
    )
    (net (code "39") (name "LOWER_SWITCH") (class "Default")
      (node (ref "JP11") (pin "2") (pinfunction "2_2") (pintype "passive"))
      (node (ref "R24") (pin "1") (pinfunction "1_1") (pintype "passive"))
      (node (ref "U1") (pin "29") (pinfunction "P2.0/TA1.1_29") (pintype "bidirectional"))
    )
    (net (code "40") (name "NU_P6.3") (class "Default")
      (node (ref "JP1") (pin "5") (pinfunction "5_5") (pintype "bidirectional"))
      (node (ref "U1") (pin "80") (pinfunction "P6.3/CB3/A3_80") (pintype "bidirectional"))
    )
    (net (code "41") (name "NU_P6.4") (class "Default")
      (node (ref "JP1") (pin "6") (pinfunction "6_6") (pintype "bidirectional"))
      (node (ref "U1") (pin "1") (pinfunction "P6.4/CB4/A4_1") (pintype "bidirectional"))
    )
    (net (code "42") (name "NU_P6.5") (class "Default")
      (node (ref "JP1") (pin "3") (pinfunction "3_3") (pintype "bidirectional"))
      (node (ref "U1") (pin "2") (pinfunction "P6.5/CB5/A5_2") (pintype "bidirectional"))
    )
    (net (code "43") (name "NU_P6.6") (class "Default")
      (node (ref "JP1") (pin "4") (pinfunction "4_4") (pintype "bidirectional"))
      (node (ref "U1") (pin "3") (pinfunction "P6.6/CB6/A6_3") (pintype "bidirectional"))
    )
    (net (code "44") (name "NU_P6.7") (class "Default")
      (node (ref "JP1") (pin "1") (pinfunction "1_1") (pintype "bidirectional"))
      (node (ref "U1") (pin "4") (pinfunction "P6.7/CB7/A7_4") (pintype "bidirectional"))
    )
    (net (code "45") (name "NU_P7.0") (class "Default")
      (node (ref "U1") (pin "5") (pinfunction "P7.0/CB8/A12_5") (pintype "bidirectional"))
    )
    (net (code "46") (name "Net-(JP4-VCC)") (class "Default")
      (node (ref "JP2") (pin "2") (pinfunction "2_2") (pintype "passive"))
      (node (ref "JP4") (pin "P$4") (pinfunction "VCC_P$4") (pintype "bidirectional"))
    )
    (net (code "47") (name "Net-(LED1-PadA)") (class "Default")
      (node (ref "LED1") (pin "A") (pinfunction "A_A") (pintype "passive"))
      (node (ref "R1") (pin "1") (pinfunction "1_1") (pintype "passive"))
    )
    (net (code "48") (name "Net-(LED2-PadA)") (class "Default")
      (node (ref "LED2") (pin "A") (pinfunction "A_A") (pintype "passive"))
      (node (ref "R2") (pin "1") (pinfunction "1_1") (pintype "passive"))
    )
    (net (code "49") (name "Net-(LED3-PadA)") (class "Default")
      (node (ref "LED3") (pin "A") (pinfunction "A_A") (pintype "passive"))
      (node (ref "R3") (pin "1") (pinfunction "1_1") (pintype "passive"))
    )
    (net (code "50") (name "Net-(LED4-PadC)") (class "Default")
      (node (ref "LED4") (pin "C") (pinfunction "C_C") (pintype "passive"))
      (node (ref "R8") (pin "2") (pinfunction "2_2") (pintype "passive"))
    )
    (net (code "51") (name "Net-(LED5-PadA)") (class "Default")
      (node (ref "LED5") (pin "A") (pinfunction "A_A") (pintype "passive"))
      (node (ref "R10") (pin "1") (pinfunction "1_1") (pintype "passive"))
    )
    (net (code "52") (name "Net-(LED6-PadA)") (class "Default")
      (node (ref "LED6") (pin "A") (pinfunction "A_A") (pintype "passive"))
      (node (ref "R11") (pin "1") (pinfunction "1_1") (pintype "passive"))
    )
    (net (code "53") (name "Net-(LED7-PadA)") (class "Default")
      (node (ref "LED7") (pin "A") (pinfunction "A_A") (pintype "passive"))
      (node (ref "R12") (pin "1") (pinfunction "1_1") (pintype "passive"))
    )
    (net (code "54") (name "Net-(LED8-PadA)") (class "Default")
      (node (ref "LED8") (pin "A") (pinfunction "A_A") (pintype "passive"))
      (node (ref "R29") (pin "1") (pinfunction "1_1") (pintype "passive"))
    )
    (net (code "55") (name "Net-(LED9-PadA)") (class "Default")
      (node (ref "LED9") (pin "A") (pinfunction "A_A") (pintype "passive"))
      (node (ref "R30") (pin "1") (pinfunction "1_1") (pintype "passive"))
    )
    (net (code "56") (name "Net-(LED10-PadA)") (class "Default")
      (node (ref "LED10") (pin "A") (pinfunction "A_A") (pintype "passive"))
      (node (ref "R31") (pin "1") (pinfunction "1_1") (pintype "passive"))
    )
    (net (code "57") (name "Net-(LED11-PadA)") (class "Default")
      (node (ref "LED11") (pin "A") (pinfunction "A_A") (pintype "passive"))
      (node (ref "R32") (pin "1") (pinfunction "1_1") (pintype "passive"))
    )
    (net (code "58") (name "Net-(LED12-PadC)") (class "Default")
      (node (ref "LED12") (pin "C") (pinfunction "C_C") (pintype "passive"))
      (node (ref "R36") (pin "1") (pinfunction "1_1") (pintype "passive"))
    )
    (net (code "59") (name "Net-(Q2A-DRAIN)") (class "Default")
      (node (ref "Q2") (pin "6") (pinfunction "DRAIN_6") (pintype "bidirectional"))
      (node (ref "Q3") (pin "1") (pinfunction "G_1") (pintype "passive"))
      (node (ref "R17") (pin "1") (pinfunction "1_1") (pintype "passive"))
    )
    (net (code "60") (name "Net-(Q2A-GATE)") (class "Default")
      (node (ref "Q2") (pin "2") (pinfunction "GATE_2") (pintype "bidirectional"))
      (node (ref "Q2") (pin "5") (pinfunction "GATE_5") (pintype "bidirectional"))
      (node (ref "R16") (pin "1") (pinfunction "1_1") (pintype "passive"))
    )
    (net (code "61") (name "Net-(Q2B-DRAIN)") (class "Default")
      (node (ref "Q2") (pin "3") (pinfunction "DRAIN_3") (pintype "bidirectional"))
      (node (ref "Q4") (pin "1") (pinfunction "G_1") (pintype "passive"))
      (node (ref "R20") (pin "1") (pinfunction "1_1") (pintype "passive"))
    )
    (net (code "62") (name "Net-(Q3-D)") (class "Default")
      (node (ref "Q3") (pin "3") (pinfunction "D_3") (pintype "passive"))
      (node (ref "R18") (pin "2") (pinfunction "2_2") (pintype "passive"))
    )
    (net (code "63") (name "Net-(Q4-D)") (class "Default")
      (node (ref "Q4") (pin "3") (pinfunction "D_3") (pintype "passive"))
      (node (ref "R21") (pin "2") (pinfunction "2_2") (pintype "passive"))
    )
    (net (code "64") (name "Net-(Q5A-GATE)") (class "Default")
      (node (ref "Q5") (pin "2") (pinfunction "GATE_2") (pintype "bidirectional"))
      (node (ref "R35") (pin "2") (pinfunction "2_2") (pintype "passive"))
      (node (ref "R37") (pin "1") (pinfunction "1_1") (pintype "passive"))
      (node (ref "U2") (pin "4") (pinfunction "4_4") (pintype "bidirectional"))
    )
    (net (code "65") (name "Net-(Q5B-DRAIN)") (class "Default")
      (node (ref "Q5") (pin "3") (pinfunction "DRAIN_3") (pintype "bidirectional"))
      (node (ref "R36") (pin "2") (pinfunction "2_2") (pintype "passive"))
    )
    (net (code "66") (name "Net-(Q6A-GATE)") (class "Default")
      (node (ref "Q6") (pin "2") (pinfunction "GATE_2") (pintype "bidirectional"))
      (node (ref "R29") (pin "2") (pinfunction "2_2") (pintype "passive"))
      (node (ref "U4") (pin "3") (pinfunction "Y_3") (pintype "bidirectional"))
    )
    (net (code "67") (name "Net-(Q6B-GATE)") (class "Default")
      (node (ref "Q6") (pin "5") (pinfunction "GATE_5") (pintype "bidirectional"))
      (node (ref "R30") (pin "2") (pinfunction "2_2") (pintype "passive"))
      (node (ref "U4") (pin "6") (pinfunction "Y_6") (pintype "bidirectional"))
    )
    (net (code "68") (name "Net-(Q7A-GATE)") (class "Default")
      (node (ref "Q7") (pin "2") (pinfunction "GATE_2") (pintype "bidirectional"))
      (node (ref "R31") (pin "2") (pinfunction "2_2") (pintype "passive"))
      (node (ref "U4") (pin "8") (pinfunction "Y_8") (pintype "bidirectional"))
    )
    (net (code "69") (name "Net-(Q7B-GATE)") (class "Default")
      (node (ref "Q7") (pin "5") (pinfunction "GATE_5") (pintype "bidirectional"))
      (node (ref "R32") (pin "2") (pinfunction "2_2") (pintype "passive"))
      (node (ref "U4") (pin "11") (pinfunction "Y_11") (pintype "bidirectional"))
    )
    (net (code "70") (name "Net-(R25-Pad1)") (class "Default")
      (node (ref "R25") (pin "1") (pinfunction "1_1") (pintype "passive"))
      (node (ref "U2") (pin "1") (pinfunction "1_1") (pintype "bidirectional"))
    )
    (net (code "71") (name "Net-(U1-AVCC1)") (class "Default")
      (node (ref "C5") (pin "1") (pinfunction "1_1") (pintype "passive"))
      (node (ref "R4") (pin "1") (pinfunction "1_1") (pintype "passive"))
      (node (ref "U1") (pin "11") (pinfunction "AVCC1_11") (pintype "bidirectional"))
    )
    (net (code "72") (name "Net-(U1-PUR)") (class "Default")
      (node (ref "R5") (pin "2") (pinfunction "2_2") (pintype "passive"))
      (node (ref "U1") (pin "63") (pinfunction "PUR_63") (pintype "bidirectional"))
    )
    (net (code "73") (name "Net-(U1-V18)") (class "Default")
      (node (ref "C7") (pin "1") (pinfunction "1_1") (pintype "passive"))
      (node (ref "U1") (pin "67") (pinfunction "V18_67") (pintype "bidirectional"))
    )
    (net (code "74") (name "Net-(U1-VCORE)") (class "Default")
      (node (ref "C4") (pin "1") (pinfunction "1_1") (pintype "passive"))
      (node (ref "U1") (pin "20") (pinfunction "VCORE_20") (pintype "bidirectional"))
    )
    (net (code "75") (name "Net-(U1-VUSB)") (class "Default")
      (node (ref "C6") (pin "1") (pinfunction "1_1") (pintype "passive"))
      (node (ref "U1") (pin "66") (pinfunction "VUSB_66") (pintype "bidirectional"))
    )
    (net (code "76") (name "Net-(U3A-Q)") (class "Default")
      (node (ref "U3") (pin "5") (pinfunction "Q_5") (pintype "bidirectional"))
      (node (ref "U4") (pin "1") (pinfunction "A_1") (pintype "bidirectional"))
    )
    (net (code "77") (name "Net-(U3A-{slash}CLR)") (class "Default")
      (node (ref "R28") (pin "2") (pinfunction "2_2") (pintype "passive"))
      (node (ref "U3") (pin "1") (pinfunction "/CLR_1") (pintype "bidirectional"))
    )
    (net (code "78") (name "Net-(U3A-{slash}PRE)") (class "Default")
      (node (ref "R27") (pin "1") (pinfunction "1_1") (pintype "passive"))
      (node (ref "U3") (pin "4") (pinfunction "/PRE_4") (pintype "bidirectional"))
    )
    (net (code "79") (name "Net-(U3A-{slash}Q)") (class "Default")
      (node (ref "U3") (pin "6") (pinfunction "/Q_6") (pintype "bidirectional"))
      (node (ref "U4") (pin "5") (pinfunction "B_5") (pintype "bidirectional"))
    )
    (net (code "80") (name "Net-(U3B-Q)") (class "Default")
      (node (ref "U3") (pin "9") (pinfunction "Q_9") (pintype "bidirectional"))
      (node (ref "U4") (pin "9") (pinfunction "A_9") (pintype "bidirectional"))
    )
    (net (code "81") (name "Net-(U3B-{slash}CLR)") (class "Default")
      (node (ref "R34") (pin "2") (pinfunction "2_2") (pintype "passive"))
      (node (ref "U3") (pin "13") (pinfunction "/CLR_13") (pintype "bidirectional"))
    )
    (net (code "82") (name "Net-(U3B-{slash}PRE)") (class "Default")
      (node (ref "R33") (pin "1") (pinfunction "1_1") (pintype "passive"))
      (node (ref "U3") (pin "10") (pinfunction "/PRE_10") (pintype "bidirectional"))
    )
    (net (code "83") (name "Net-(U3B-{slash}Q)") (class "Default")
      (node (ref "U3") (pin "8") (pinfunction "/Q_8") (pintype "bidirectional"))
      (node (ref "U4") (pin "13") (pinfunction "B_13") (pintype "bidirectional"))
    )
    (net (code "84") (name "RC_PWR") (class "Default")
      (node (ref "JP6") (pin "2") (pinfunction "2_2") (pintype "passive"))
      (node (ref "JP8") (pin "1") (pinfunction "1_1") (pintype "passive"))
    )
    (net (code "85") (name "RC_RXD") (class "Default")
      (node (ref "R14") (pin "2") (pinfunction "2_2") (pintype "passive"))
      (node (ref "SJ3") (pin "3") (pinfunction "3_3") (pintype "passive"))
      (node (ref "SJ4") (pin "1") (pinfunction "1_1") (pintype "passive"))
      (node (ref "U1") (pin "52") (pinfunction "P4.5/PM_UCA1RXD/PM_UCA1SOMI_52") (pintype "bidirectional"))
    )
    (net (code "86") (name "RC_S1") (class "Default")
      (node (ref "JP6") (pin "3") (pinfunction "3_3") (pintype "passive"))
      (node (ref "SJ3") (pin "2") (pinfunction "2_2") (pintype "passive"))
    )
    (net (code "87") (name "RC_S2") (class "Default")
      (node (ref "JP6") (pin "4") (pinfunction "4_4") (pintype "passive"))
      (node (ref "SJ4") (pin "2") (pinfunction "2_2") (pintype "passive"))
    )
    (net (code "88") (name "RC_S3") (class "Default")
      (node (ref "JP6") (pin "5") (pinfunction "5_5") (pintype "passive"))
      (node (ref "R13") (pin "2") (pinfunction "2_2") (pintype "passive"))
    )
    (net (code "89") (name "RC_TXD") (class "Default")
      (node (ref "R15") (pin "2") (pinfunction "2_2") (pintype "passive"))
      (node (ref "SJ3") (pin "1") (pinfunction "1_1") (pintype "passive"))
      (node (ref "SJ4") (pin "3") (pinfunction "3_3") (pintype "passive"))
      (node (ref "U1") (pin "51") (pinfunction "P4.4/PM_UCA1TXD/PM_UCA1SIMO_51") (pintype "bidirectional"))
    )
    (net (code "90") (name "RXI") (class "Default")
      (node (ref "JP4") (pin "P$3") (pinfunction "RXI_P$3") (pintype "bidirectional"))
      (node (ref "SJ2") (pin "2") (pinfunction "2_2") (pintype "passive"))
    )
    (net (code "91") (name "SBWTCK") (class "Default")
      (node (ref "JP3") (pin "7") (pinfunction "7_7") (pintype "bidirectional"))
      (node (ref "U1") (pin "71") (pinfunction "TEST/SBWTCK_71") (pintype "bidirectional"))
    )
    (net (code "92") (name "SBWTDIO") (class "Default")
      (node (ref "C8") (pin "1") (pinfunction "1_1") (pintype "passive"))
      (node (ref "JP3") (pin "1") (pinfunction "1_1") (pintype "bidirectional"))
      (node (ref "R6") (pin "1") (pinfunction "1_1") (pintype "passive"))
      (node (ref "S1") (pin "2") (pinfunction "2_2") (pintype "bidirectional"))
      (node (ref "U1") (pin "76") (pinfunction "/RST/NMI/SBWTDIO_76") (pintype "bidirectional"))
    )
    (net (code "93") (name "STAT_ERR") (class "Default")
      (node (ref "R12") (pin "2") (pinfunction "2_2") (pintype "passive"))
      (node (ref "U1") (pin "54") (pinfunction "P4.7/PM_NONE_54") (pintype "bidirectional"))
    )
    (net (code "94") (name "STAT_OK") (class "Default")
      (node (ref "R10") (pin "2") (pinfunction "2_2") (pintype "passive"))
      (node (ref "U1") (pin "56") (pinfunction "P5.7/TB0.1_56") (pintype "bidirectional"))
    )
    (net (code "95") (name "STAT_WARN") (class "Default")
      (node (ref "R11") (pin "2") (pinfunction "2_2") (pintype "passive"))
      (node (ref "U1") (pin "55") (pinfunction "P5.6/TB0.0_55") (pintype "bidirectional"))
    )
    (net (code "96") (name "STEPPER_DIR") (class "Default")
      (node (ref "JP7") (pin "2") (pinfunction "2_2") (pintype "passive"))
      (node (ref "U1") (pin "6") (pinfunction "P7.1/CB9/A13_6") (pintype "bidirectional"))
    )
    (net (code "97") (name "STEPPER_EN") (class "Default")
      (node (ref "JP7") (pin "3") (pinfunction "3_3") (pintype "passive"))
      (node (ref "U1") (pin "7") (pinfunction "P7.2/CB10/A14_7") (pintype "bidirectional"))
    )
    (net (code "98") (name "STEPPER_STEP") (class "Default")
      (node (ref "JP7") (pin "1") (pinfunction "1_1") (pintype "passive"))
      (node (ref "U1") (pin "23") (pinfunction "P1.2/TA0.1_23") (pintype "bidirectional"))
    )
    (net (code "99") (name "TXO") (class "Default")
      (node (ref "JP4") (pin "P$2") (pinfunction "TXO_P$2") (pintype "bidirectional"))
      (node (ref "SJ1") (pin "2") (pinfunction "2_2") (pintype "passive"))
    )
    (net (code "100") (name "UPPER_SWITCH") (class "Default")
      (node (ref "JP10") (pin "2") (pinfunction "2_2") (pintype "passive"))
      (node (ref "R23") (pin "1") (pinfunction "1_1") (pintype "passive"))
      (node (ref "U1") (pin "30") (pinfunction "P2.1/TA1.2_30") (pintype "bidirectional"))
    )
    (net (code "101") (name "VCC_TARGET") (class "Default")
      (node (ref "JP3") (pin "4") (pinfunction "4_4") (pintype "bidirectional"))
      (node (ref "JP5") (pin "1") (pinfunction "1_1") (pintype "passive"))
    )
    (net (code "102") (name "VCC_TOOL") (class "Default")
      (node (ref "JP3") (pin "2") (pinfunction "2_2") (pintype "bidirectional"))
      (node (ref "JP5") (pin "3") (pinfunction "3_3") (pintype "passive"))
    )
    (net (code "103") (name "VOC") (class "Default")
      (node (ref "JP15") (pin "7") (pinfunction "7_7") (pintype "passive"))
    )
    (net (code "104") (name "XT2IN") (class "Default")
      (node (ref "C9") (pin "1") (pinfunction "1_1") (pintype "passive"))
      (node (ref "U1") (pin "69") (pinfunction "P5.2/XT2IN_69") (pintype "bidirectional"))
      (node (ref "Y1") (pin "1") (pinfunction "1_1") (pintype "passive"))
    )
    (net (code "105") (name "XT2OUT") (class "Default")
      (node (ref "C10") (pin "1") (pinfunction "1_1") (pintype "passive"))
      (node (ref "U1") (pin "70") (pinfunction "P5.3/XT2OUT_70") (pintype "bidirectional"))
      (node (ref "Y1") (pin "2") (pinfunction "2_2") (pintype "passive"))
    )
    (net (code "106") (name "unconnected-(JP3-Pad3)") (class "Default")
      (node (ref "JP3") (pin "3") (pinfunction "3_3") (pintype "bidirectional"))
    )
    (net (code "107") (name "unconnected-(JP3-Pad5)") (class "Default")
      (node (ref "JP3") (pin "5") (pinfunction "5_5") (pintype "bidirectional"))
    )
    (net (code "108") (name "unconnected-(JP3-Pad6)") (class "Default")
      (node (ref "JP3") (pin "6") (pinfunction "6_6") (pintype "bidirectional"))
    )
    (net (code "109") (name "unconnected-(JP3-Pad8)") (class "Default")
      (node (ref "JP3") (pin "8") (pinfunction "8_8") (pintype "bidirectional"))
    )
    (net (code "110") (name "unconnected-(JP3-Pad10)") (class "Default")
      (node (ref "JP3") (pin "10") (pinfunction "10_10") (pintype "bidirectional"))
    )
    (net (code "111") (name "unconnected-(JP3-Pad11)") (class "Default")
      (node (ref "JP3") (pin "11") (pinfunction "11_11") (pintype "bidirectional"))
    )
    (net (code "112") (name "unconnected-(JP3-Pad12)") (class "Default")
      (node (ref "JP3") (pin "12") (pinfunction "12_12") (pintype "bidirectional"))
    )
    (net (code "113") (name "unconnected-(JP3-Pad13)") (class "Default")
      (node (ref "JP3") (pin "13") (pinfunction "13_13") (pintype "bidirectional"))
    )
    (net (code "114") (name "unconnected-(JP3-Pad14)") (class "Default")
      (node (ref "JP3") (pin "14") (pinfunction "14_14") (pintype "bidirectional"))
    )
    (net (code "115") (name "unconnected-(JP4-CTS-PadP$5)") (class "Default")
      (node (ref "JP4") (pin "P$5") (pinfunction "CTS_P$5") (pintype "bidirectional"))
    )
    (net (code "116") (name "unconnected-(JP4-DTR-PadP$1)") (class "Default")
      (node (ref "JP4") (pin "P$1") (pinfunction "DTR_P$1") (pintype "bidirectional"))
    )
    (net (code "117") (name "unconnected-(U1-P1.1{slash}TA0.0-Pad22)") (class "Default")
      (node (ref "U1") (pin "22") (pinfunction "P1.1/TA0.0_22") (pintype "bidirectional"))
    )
    (net (code "118") (name "unconnected-(U1-P1.5{slash}TA0.4-Pad26)") (class "Default")
      (node (ref "U1") (pin "26") (pinfunction "P1.5/TA0.4_26") (pintype "bidirectional"))
    )
    (net (code "119") (name "unconnected-(U1-P1.6{slash}TA1CLK{slash}CBOUT-Pad27)") (class "Default")
      (node (ref "U1") (pin "27") (pinfunction "P1.6/TA1CLK/CBOUT_27") (pintype "bidirectional"))
    )
    (net (code "120") (name "unconnected-(U1-P1.7{slash}TA1.0-Pad28)") (class "Default")
      (node (ref "U1") (pin "28") (pinfunction "P1.7/TA1.0_28") (pintype "bidirectional"))
    )
    (net (code "121") (name "unconnected-(U1-P3.5{slash}TB0.5-Pad42)") (class "Default")
      (node (ref "U1") (pin "42") (pinfunction "P3.5/TB0.5_42") (pintype "bidirectional"))
    )
    (net (code "122") (name "unconnected-(U1-P3.6{slash}TB0.6-Pad43)") (class "Default")
      (node (ref "U1") (pin "43") (pinfunction "P3.6/TB0.6_43") (pintype "bidirectional"))
    )
    (net (code "123") (name "unconnected-(U1-P3.7{slash}TB0OUTH{slash}SVMOUT-Pad44)") (class "Default")
      (node (ref "U1") (pin "44") (pinfunction "P3.7/TB0OUTH/SVMOUT_44") (pintype "bidirectional"))
    )
    (net (code "124") (name "unconnected-(U1-P4.0{slash}PM_UCB1STE{slash}PM_UCA1CLK-Pad45)") (class "Default")
      (node (ref "U1") (pin "45") (pinfunction "P4.0/PM_UCB1STE/PM_UCA1CLK_45") (pintype "bidirectional"))
    )
    (net (code "125") (name "unconnected-(U1-P4.1{slash}PM_UCB1SIMO{slash}PM_UCB1SDA-Pad46)") (class "Default")
      (node (ref "U1") (pin "46") (pinfunction "P4.1/PM_UCB1SIMO/PM_UCB1SDA_46") (pintype "bidirectional"))
    )
    (net (code "126") (name "unconnected-(U1-P4.2{slash}PM_UCB1SOMI{slash}PM_UCB1SCL-Pad47)") (class "Default")
      (node (ref "U1") (pin "47") (pinfunction "P4.2/PM_UCB1SOMI/PM_UCB1SCL_47") (pintype "bidirectional"))
    )
    (net (code "127") (name "unconnected-(U1-P4.3{slash}PM_UCB1CLK{slash}PM_UCA1STE-Pad48)") (class "Default")
      (node (ref "U1") (pin "48") (pinfunction "P4.3/PM_UCB1CLK/PM_UCA1STE_48") (pintype "bidirectional"))
    )
    (net (code "128") (name "unconnected-(U1-P4.6{slash}PM_NONE-Pad53)") (class "Default")
      (node (ref "U1") (pin "53") (pinfunction "P4.6/PM_NONE_53") (pintype "bidirectional"))
    )
    (net (code "129") (name "unconnected-(U1-P5.4{slash}XIN-Pad12)") (class "Default")
      (node (ref "U1") (pin "12") (pinfunction "P5.4/XIN_12") (pintype "bidirectional"))
    )
    (net (code "130") (name "unconnected-(U1-P5.5{slash}XOUT-Pad13)") (class "Default")
      (node (ref "U1") (pin "13") (pinfunction "P5.5/XOUT_13") (pintype "bidirectional"))
    )
    (net (code "131") (name "unconnected-(U1-P7.3{slash}CB11{slash}A15-Pad8)") (class "Default")
      (node (ref "U1") (pin "8") (pinfunction "P7.3/CB11/A15_8") (pintype "bidirectional"))
    )
    (net (code "132") (name "unconnected-(U1-P8.0-Pad15)") (class "Default")
      (node (ref "U1") (pin "15") (pinfunction "P8.0_15") (pintype "bidirectional"))
    )
    (net (code "133") (name "unconnected-(U1-P8.1-Pad16)") (class "Default")
      (node (ref "U1") (pin "16") (pinfunction "P8.1_16") (pintype "bidirectional"))
    )
    (net (code "134") (name "unconnected-(U1-P8.2-Pad17)") (class "Default")
      (node (ref "U1") (pin "17") (pinfunction "P8.2_17") (pintype "bidirectional"))
    )
    (net (code "135") (name "unconnected-(U1-PJ.0{slash}TDO-Pad72)") (class "Default")
      (node (ref "U1") (pin "72") (pinfunction "PJ.0/TDO_72") (pintype "bidirectional"))
    )
    (net (code "136") (name "unconnected-(U1-PJ.1{slash}TDI{slash}TCK-Pad73)") (class "Default")
      (node (ref "U1") (pin "73") (pinfunction "PJ.1/TDI/TCK_73") (pintype "bidirectional"))
    )
    (net (code "137") (name "unconnected-(U1-PJ.2{slash}TMS-Pad74)") (class "Default")
      (node (ref "U1") (pin "74") (pinfunction "PJ.2/TMS_74") (pintype "bidirectional"))
    )
    (net (code "138") (name "unconnected-(U1-PJ.3{slash}TCK-Pad75)") (class "Default")
      (node (ref "U1") (pin "75") (pinfunction "PJ.3/TCK_75") (pintype "bidirectional"))
    )
    (net (code "139") (name "unconnected-(U1-PU.0{slash}DP-Pad62)") (class "Default")
      (node (ref "U1") (pin "62") (pinfunction "PU.0/DP_62") (pintype "bidirectional"))
    )
    (net (code "140") (name "unconnected-(U1-PU.1{slash}DM-Pad64)") (class "Default")
      (node (ref "U1") (pin "64") (pinfunction "PU.1/DM_64") (pintype "bidirectional"))
    )
    (net (code "141") (name "unconnected-(U1-VBUS-Pad65)") (class "Default")
      (node (ref "U1") (pin "65") (pinfunction "VBUS_65") (pintype "bidirectional"))
    )
  )
)
